# usb-dongle.net
KiCad netlist of a schematic drawn in EAGLE
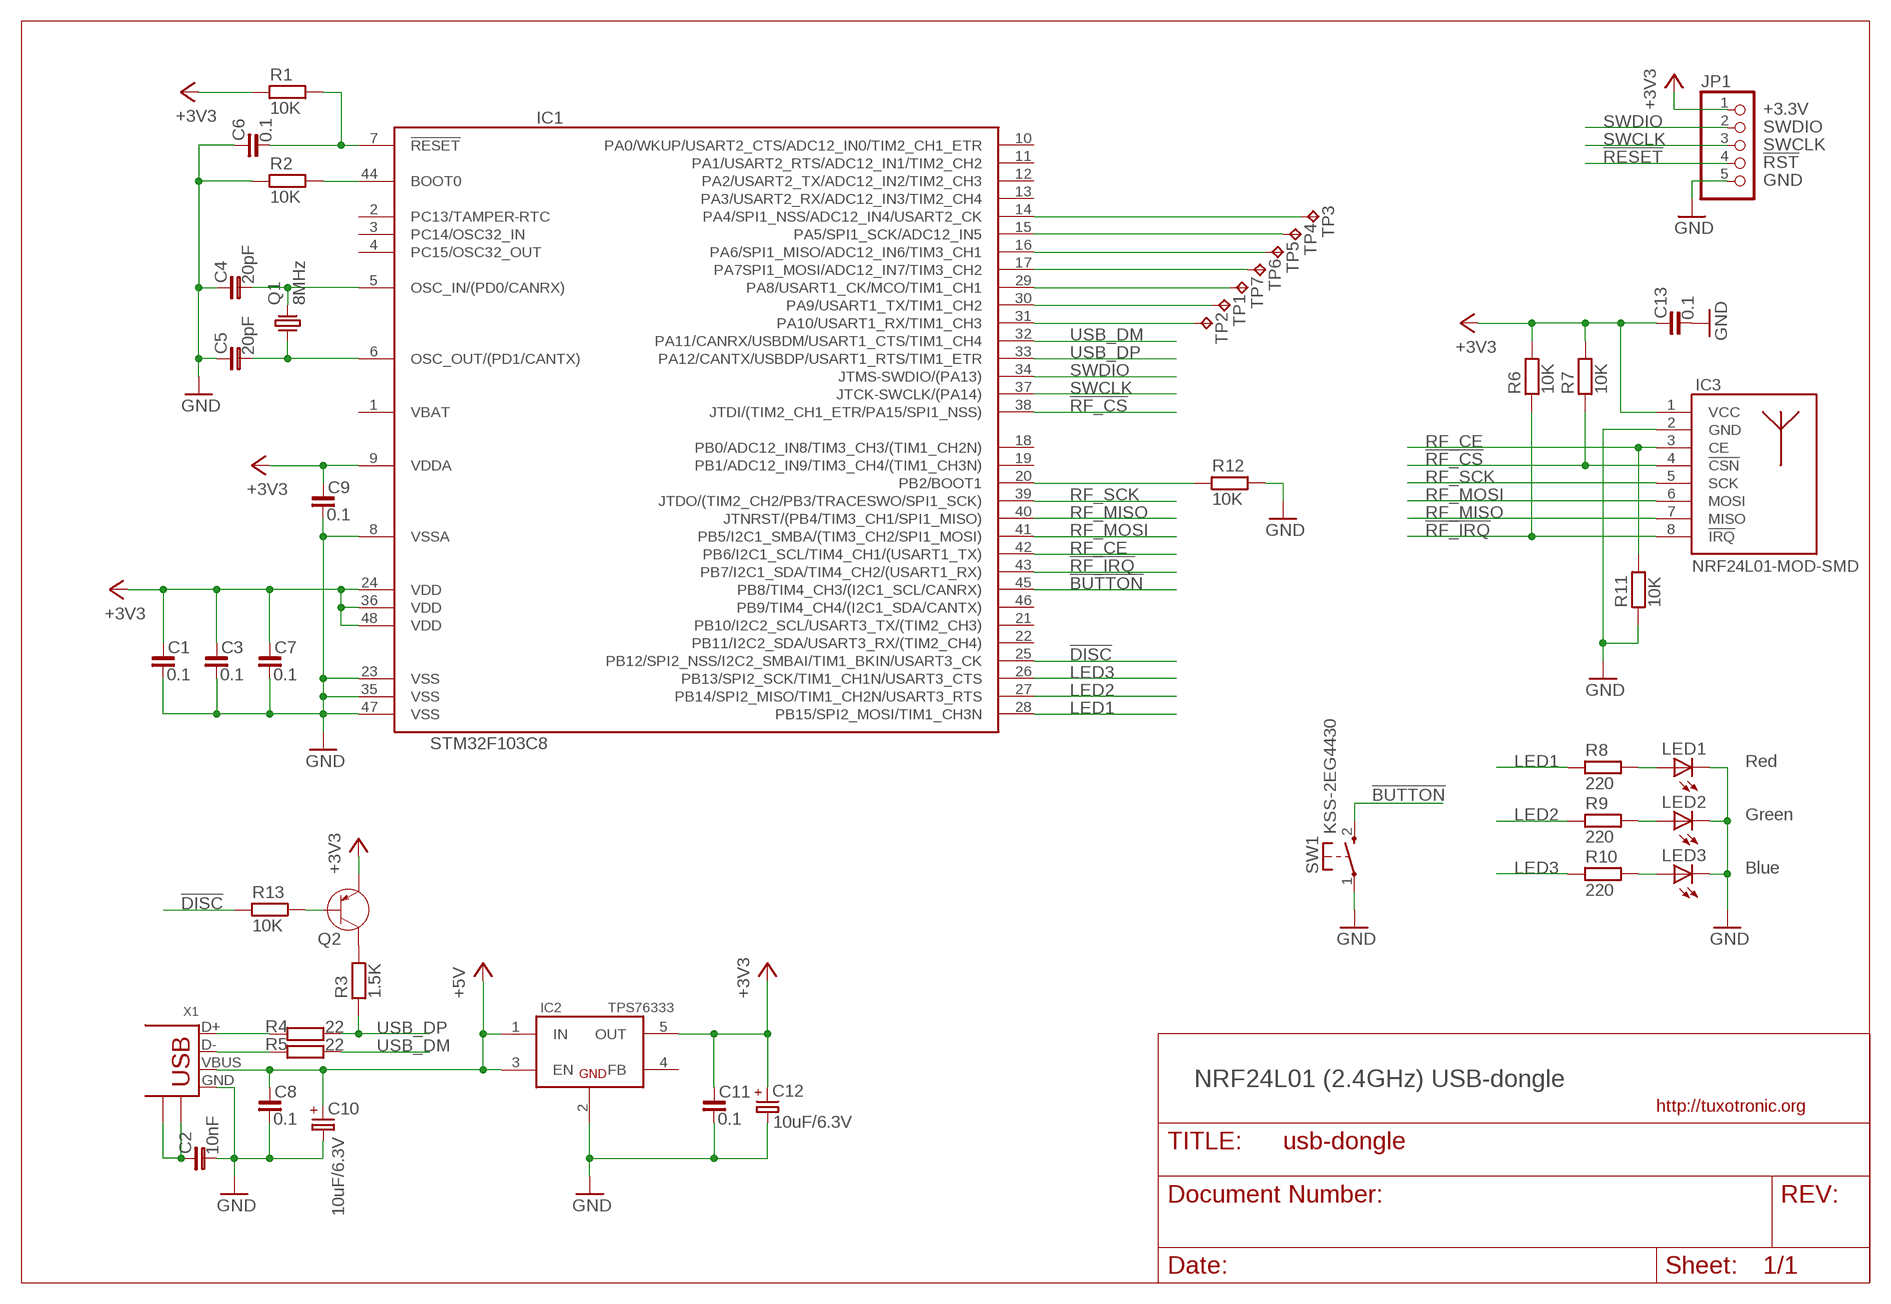
[diagram p0: schematic, sheet 1]

(export (version "E")
  (design (tool "Eeschema 10.0.6"))
  (components
    (comp (ref "C1")
      (value "0.1")
      (footprint "eagle-import:C0603")
      (libsource (lib "eagle-import") (part "C_0603"))
    )
    (comp (ref "C2")
      (value "10nF")
      (footprint "eagle-import:C1206")
      (libsource (lib "eagle-import") (part "C_1206"))
    )
    (comp (ref "C3")
      (value "0.1")
      (footprint "eagle-import:C0603")
      (libsource (lib "eagle-import") (part "C_0603"))
    )
    (comp (ref "C4")
      (value "20pF")
      (footprint "eagle-import:C0603")
      (libsource (lib "eagle-import") (part "C_0603"))
    )
    (comp (ref "C5")
      (value "20pF")
      (footprint "eagle-import:C0603")
      (libsource (lib "eagle-import") (part "C_0603"))
    )
    (comp (ref "C6")
      (value "0.1")
      (footprint "eagle-import:C0603")
      (libsource (lib "eagle-import") (part "C_0603"))
    )
    (comp (ref "C7")
      (value "0.1")
      (footprint "eagle-import:C0603")
      (libsource (lib "eagle-import") (part "C_0603"))
    )
    (comp (ref "C8")
      (value "0.1")
      (footprint "eagle-import:C0603")
      (libsource (lib "eagle-import") (part "C_0603"))
    )
    (comp (ref "C9")
      (value "0.1")
      (footprint "eagle-import:C0603")
      (libsource (lib "eagle-import") (part "C_0603"))
    )
    (comp (ref "C10")
      (value "10uF/6.3V")
      (footprint "eagle-import:SMC_B")
      (libsource (lib "eagle-import") (part "CP_SMCB"))
    )
    (comp (ref "C11")
      (value "0.1")
      (footprint "eagle-import:C0603")
      (libsource (lib "eagle-import") (part "C_0603"))
    )
    (comp (ref "C12")
      (value "10uF/6.3V")
      (footprint "eagle-import:SMC_B")
      (libsource (lib "eagle-import") (part "CP_SMCB"))
    )
    (comp (ref "C13")
      (value "0.1")
      (footprint "eagle-import:C0603")
      (libsource (lib "eagle-import") (part "C_0603"))
    )
    (comp (ref "IC1")
      (value "STM32F103C8")
      (footprint "eagle-import:LQFP48")
      (libsource (lib "eagle-import") (part "STM32F103C8"))
    )
    (comp (ref "IC2")
      (value "TPS76333")
      (footprint "eagle-import:SOT23-5")
      (libsource (lib "eagle-import") (part "TPS76333"))
    )
    (comp (ref "IC3")
      (value "NRF24L01-MOD-SMD")
      (footprint "eagle-import:SMD8-MODULE")
      (libsource (lib "eagle-import") (part "NRF24L01-MOD-SMD"))
    )
    (comp (ref "JP1")
      (value "SWD-5_2.00")
      (footprint "eagle-import:1X05M")
      (libsource (lib "eagle-import") (part "SWD-5_2.00"))
    )
    (comp (ref "LED1")
      (value "LEDCHIPLED_0805")
      (footprint "eagle-import:CHIPLED_0805")
      (libsource (lib "eagle-import") (part "LEDCHIPLED_0805"))
    )
    (comp (ref "LED2")
      (value "LEDCHIPLED_0805")
      (footprint "eagle-import:CHIPLED_0805")
      (libsource (lib "eagle-import") (part "LEDCHIPLED_0805"))
    )
    (comp (ref "LED3")
      (value "LEDCHIPLED_0805")
      (footprint "eagle-import:CHIPLED_0805")
      (libsource (lib "eagle-import") (part "LEDCHIPLED_0805"))
    )
    (comp (ref "Q1")
      (value "8MHz")
      (footprint "eagle-import:HC49_S")
      (libsource (lib "eagle-import") (part "CRYSTAL-HC49S"))
    )
    (comp (ref "Q2")
      (value "PNP-SOT23")
      (footprint "eagle-import:SOT23")
      (libsource (lib "eagle-import") (part "PNP-SOT23"))
    )
    (comp (ref "R1")
      (value "10K")
      (footprint "eagle-import:R0603")
      (libsource (lib "eagle-import") (part "R_0603"))
    )
    (comp (ref "R2")
      (value "10K")
      (footprint "eagle-import:R0603")
      (libsource (lib "eagle-import") (part "R_0603"))
    )
    (comp (ref "R3")
      (value "1.5K")
      (footprint "eagle-import:R0603")
      (libsource (lib "eagle-import") (part "R_0603"))
    )
    (comp (ref "R4")
      (value "22")
      (footprint "eagle-import:R0603")
      (libsource (lib "eagle-import") (part "R_0603"))
    )
    (comp (ref "R5")
      (value "22")
      (footprint "eagle-import:R0603")
      (libsource (lib "eagle-import") (part "R_0603"))
    )
    (comp (ref "R6")
      (value "10K")
      (footprint "eagle-import:R0603")
      (libsource (lib "eagle-import") (part "R_0603"))
    )
    (comp (ref "R7")
      (value "10K")
      (footprint "eagle-import:R0603")
      (libsource (lib "eagle-import") (part "R_0603"))
    )
    (comp (ref "R8")
      (value "220")
      (footprint "eagle-import:R0603")
      (libsource (lib "eagle-import") (part "R_0603"))
    )
    (comp (ref "R9")
      (value "220")
      (footprint "eagle-import:R0603")
      (libsource (lib "eagle-import") (part "R_0603"))
    )
    (comp (ref "R10")
      (value "220")
      (footprint "eagle-import:R0603")
      (libsource (lib "eagle-import") (part "R_0603"))
    )
    (comp (ref "R11")
      (value "10K")
      (footprint "eagle-import:R0603")
      (libsource (lib "eagle-import") (part "R_0603"))
    )
    (comp (ref "R12")
      (value "10K")
      (footprint "eagle-import:R0603")
      (libsource (lib "eagle-import") (part "R_0603"))
    )
    (comp (ref "R13")
      (value "10K")
      (footprint "eagle-import:R0603")
      (libsource (lib "eagle-import") (part "R_0603"))
    )
    (comp (ref "SW1")
      (value "KSS-2EG4430")
      (footprint "eagle-import:KSS-2EG4430")
      (libsource (lib "eagle-import") (part "KSS-2EG4430"))
    )
    (comp (ref "TP1")
      (value "TPB1,27")
      (footprint "eagle-import:B1,27")
      (libsource (lib "eagle-import") (part "TPB1,27"))
    )
    (comp (ref "TP2")
      (value "TPB1,27")
      (footprint "eagle-import:B1,27")
      (libsource (lib "eagle-import") (part "TPB1,27"))
    )
    (comp (ref "TP3")
      (value "TPB1,27")
      (footprint "eagle-import:B1,27")
      (libsource (lib "eagle-import") (part "TPB1,27"))
    )
    (comp (ref "TP4")
      (value "TPB1,27")
      (footprint "eagle-import:B1,27")
      (libsource (lib "eagle-import") (part "TPB1,27"))
    )
    (comp (ref "TP5")
      (value "TPB1,27")
      (footprint "eagle-import:B1,27")
      (libsource (lib "eagle-import") (part "TPB1,27"))
    )
    (comp (ref "TP6")
      (value "TPB1,27")
      (footprint "eagle-import:B1,27")
      (libsource (lib "eagle-import") (part "TPB1,27"))
    )
    (comp (ref "TP7")
      (value "TPB1,27")
      (footprint "eagle-import:B1,27")
      (libsource (lib "eagle-import") (part "TPB1,27"))
    )
    (comp (ref "X1")
      (value "USB-MALE-A-H")
      (footprint "eagle-import:USB-A-MH")
      (libsource (lib "eagle-import") (part "USB-MALE-A-H"))
    )
  )
  (nets
    (net (code "1") (name "+3V3") (class "Default")
      (node (ref "C1") (pin "1") (pinfunction "1_1") (pintype "passive"))
      (node (ref "C11") (pin "1") (pinfunction "1_1") (pintype "passive"))
      (node (ref "C12") (pin "+") (pinfunction "+_+") (pintype "passive"))
      (node (ref "C13") (pin "1") (pinfunction "1_1") (pintype "passive"))
      (node (ref "C3") (pin "1") (pinfunction "1_1") (pintype "passive"))
      (node (ref "C7") (pin "1") (pinfunction "1_1") (pintype "passive"))
      (node (ref "C9") (pin "1") (pinfunction "1_1") (pintype "passive"))
      (node (ref "IC1") (pin "24") (pinfunction "VDD_24") (pintype "power_in"))
      (node (ref "IC1") (pin "36") (pinfunction "VDD_36") (pintype "power_in"))
      (node (ref "IC1") (pin "48") (pinfunction "VDD_48") (pintype "power_in"))
      (node (ref "IC1") (pin "9") (pinfunction "VDDA_9") (pintype "power_in"))
      (node (ref "IC2") (pin "5") (pinfunction "OUT_5") (pintype "power_in"))
      (node (ref "IC3") (pin "1") (pinfunction "VCC_1") (pintype "power_in"))
      (node (ref "JP1") (pin "1") (pinfunction "1_1") (pintype "passive"))
      (node (ref "Q2") (pin "2") (pinfunction "E_2") (pintype "passive"))
      (node (ref "R1") (pin "1") (pinfunction "1_1") (pintype "passive"))
      (node (ref "R6") (pin "2") (pinfunction "2_2") (pintype "passive"))
      (node (ref "R7") (pin "2") (pinfunction "2_2") (pintype "passive"))
    )
    (net (code "2") (name "+5V") (class "Default")
      (node (ref "C10") (pin "+") (pinfunction "+_+") (pintype "passive"))
      (node (ref "C8") (pin "1") (pinfunction "1_1") (pintype "passive"))
      (node (ref "IC2") (pin "1") (pinfunction "IN_1") (pintype "power_in"))
      (node (ref "IC2") (pin "3") (pinfunction "EN_3") (pintype "input"))
      (node (ref "X1") (pin "VBUS") (pinfunction "VBUS_VBUS") (pintype "passive"))
    )
    (net (code "3") (name "/LED1") (class "Default")
      (node (ref "IC1") (pin "28") (pinfunction "PB15/SPI2_MOSI/TIM1_CH3N_28") (pintype "bidirectional"))
      (node (ref "R8") (pin "1") (pinfunction "1_1") (pintype "passive"))
    )
    (net (code "4") (name "/LED2") (class "Default")
      (node (ref "IC1") (pin "27") (pinfunction "PB14/SPI2_MISO/TIM1_CH2N/USART3_RTS_27") (pintype "bidirectional"))
      (node (ref "R9") (pin "1") (pinfunction "1_1") (pintype "passive"))
    )
    (net (code "5") (name "/LED3") (class "Default")
      (node (ref "IC1") (pin "26") (pinfunction "PB13/SPI2_SCK/TIM1_CH1N/USART3_CTS_26") (pintype "bidirectional"))
      (node (ref "R10") (pin "1") (pinfunction "1_1") (pintype "passive"))
    )
    (net (code "6") (name "/RF_CE") (class "Default")
      (node (ref "IC1") (pin "42") (pinfunction "PB6/I2C1_SCL/TIM4_CH1/(USART1_TX)_42") (pintype "bidirectional"))
      (node (ref "IC3") (pin "3") (pinfunction "CE_3") (pintype "input"))
      (node (ref "R11") (pin "2") (pinfunction "2_2") (pintype "passive"))
    )
    (net (code "7") (name "/RF_MISO") (class "Default")
      (node (ref "IC1") (pin "40") (pinfunction "JTNRST/(PB4/TIM3_CH1/SPI1_MISO)_40") (pintype "bidirectional"))
      (node (ref "IC3") (pin "7") (pinfunction "MISO_7") (pintype "output"))
    )
    (net (code "8") (name "/RF_MOSI") (class "Default")
      (node (ref "IC1") (pin "41") (pinfunction "PB5/I2C1_SMBA/(TIM3_CH2/SPI1_MOSI)_41") (pintype "bidirectional"))
      (node (ref "IC3") (pin "6") (pinfunction "MOSI_6") (pintype "input"))
    )
    (net (code "9") (name "/RF_SCK") (class "Default")
      (node (ref "IC1") (pin "39") (pinfunction "JTDO/(TIM2_CH2/PB3/TRACESWO/SPI1_SCK)_39") (pintype "bidirectional"))
      (node (ref "IC3") (pin "5") (pinfunction "SCK_5") (pintype "input"))
    )
    (net (code "10") (name "/SWCLK") (class "Default")
      (node (ref "IC1") (pin "37") (pinfunction "JTCK-SWCLK/(PA14)_37") (pintype "bidirectional"))
      (node (ref "JP1") (pin "3") (pinfunction "3_3") (pintype "passive"))
    )
    (net (code "11") (name "/SWDIO") (class "Default")
      (node (ref "IC1") (pin "34") (pinfunction "JTMS-SWDIO/(PA13)_34") (pintype "bidirectional"))
      (node (ref "JP1") (pin "2") (pinfunction "2_2") (pintype "passive"))
    )
    (net (code "12") (name "/USB_DM") (class "Default")
      (node (ref "IC1") (pin "32") (pinfunction "PA11/CANRX/USBDM/USART1_CTS/TIM1_CH4_32") (pintype "bidirectional"))
      (node (ref "R5") (pin "2") (pinfunction "2_2") (pintype "passive"))
    )
    (net (code "13") (name "/USB_DP") (class "Default")
      (node (ref "IC1") (pin "33") (pinfunction "PA12/CANTX/USBDP/USART1_RTS/TIM1_ETR_33") (pintype "bidirectional"))
      (node (ref "R3") (pin "1") (pinfunction "1_1") (pintype "passive"))
      (node (ref "R4") (pin "2") (pinfunction "2_2") (pintype "passive"))
    )
    (net (code "14") (name "/VBAT") (class "Default")
      (node (ref "IC1") (pin "1") (pinfunction "VBAT_1") (pintype "power_in"))
    )
    (net (code "15") (name "/~{BUTTON}") (class "Default")
      (node (ref "IC1") (pin "45") (pinfunction "PB8/TIM4_CH3/(I2C1_SCL/CANRX)_45") (pintype "bidirectional"))
      (node (ref "SW1") (pin "2") (pinfunction "S_2") (pintype "passive"))
    )
    (net (code "16") (name "/~{DISC}") (class "Default")
      (node (ref "IC1") (pin "25") (pinfunction "PB12/SPI2_NSS/I2C2_SMBAI/TIM1_BKIN/USART3_CK_25") (pintype "bidirectional"))
      (node (ref "R13") (pin "1") (pinfunction "1_1") (pintype "passive"))
    )
    (net (code "17") (name "/~{RESET}") (class "Default")
      (node (ref "C6") (pin "2") (pinfunction "2_2") (pintype "passive"))
      (node (ref "IC1") (pin "7") (pinfunction "~{RESET}_7") (pintype "input"))
      (node (ref "JP1") (pin "4") (pinfunction "4_4") (pintype "passive"))
      (node (ref "R1") (pin "2") (pinfunction "2_2") (pintype "passive"))
    )
    (net (code "18") (name "/~{RF_CS}") (class "Default")
      (node (ref "IC1") (pin "38") (pinfunction "JTDI/(TIM2_CH1_ETR/PA15/SPI1_NSS)_38") (pintype "bidirectional"))
      (node (ref "IC3") (pin "4") (pinfunction "~{CSN}_4") (pintype "input"))
      (node (ref "R7") (pin "1") (pinfunction "1_1") (pintype "passive"))
    )
    (net (code "19") (name "/~{RF_IRQ}") (class "Default")
      (node (ref "IC1") (pin "43") (pinfunction "PB7/I2C1_SDA/TIM4_CH2/(USART1_RX)_43") (pintype "bidirectional"))
      (node (ref "IC3") (pin "8") (pinfunction "~{IRQ}_8") (pintype "open_collector"))
      (node (ref "R6") (pin "1") (pinfunction "1_1") (pintype "passive"))
    )
    (net (code "20") (name "GND") (class "Default")
      (node (ref "C1") (pin "2") (pinfunction "2_2") (pintype "passive"))
      (node (ref "C10") (pin "-") (pinfunction "-_-") (pintype "passive"))
      (node (ref "C11") (pin "2") (pinfunction "2_2") (pintype "passive"))
      (node (ref "C12") (pin "-") (pinfunction "-_-") (pintype "passive"))
      (node (ref "C13") (pin "2") (pinfunction "2_2") (pintype "passive"))
      (node (ref "C2") (pin "2") (pinfunction "2_2") (pintype "passive"))
      (node (ref "C3") (pin "2") (pinfunction "2_2") (pintype "passive"))
      (node (ref "C4") (pin "1") (pinfunction "1_1") (pintype "passive"))
      (node (ref "C5") (pin "1") (pinfunction "1_1") (pintype "passive"))
      (node (ref "C6") (pin "1") (pinfunction "1_1") (pintype "passive"))
      (node (ref "C7") (pin "2") (pinfunction "2_2") (pintype "passive"))
      (node (ref "C8") (pin "2") (pinfunction "2_2") (pintype "passive"))
      (node (ref "C9") (pin "2") (pinfunction "2_2") (pintype "passive"))
      (node (ref "IC1") (pin "23") (pinfunction "VSS_23") (pintype "power_in"))
      (node (ref "IC1") (pin "35") (pinfunction "VSS_35") (pintype "power_in"))
      (node (ref "IC1") (pin "47") (pinfunction "VSS_47") (pintype "power_in"))
      (node (ref "IC1") (pin "8") (pinfunction "VSSA_8") (pintype "power_in"))
      (node (ref "IC2") (pin "2") (pinfunction "GND_2") (pintype "power_in"))
      (node (ref "IC3") (pin "2") (pinfunction "GND_2") (pintype "power_in"))
      (node (ref "JP1") (pin "5") (pinfunction "5_5") (pintype "passive"))
      (node (ref "LED1") (pin "C") (pinfunction "C_C") (pintype "passive"))
      (node (ref "LED2") (pin "C") (pinfunction "C_C") (pintype "passive"))
      (node (ref "LED3") (pin "C") (pinfunction "C_C") (pintype "passive"))
      (node (ref "R11") (pin "1") (pinfunction "1_1") (pintype "passive"))
      (node (ref "R12") (pin "2") (pinfunction "2_2") (pintype "passive"))
      (node (ref "R2") (pin "1") (pinfunction "1_1") (pintype "passive"))
      (node (ref "SW1") (pin "1") (pinfunction "P_1") (pintype "passive"))
      (node (ref "X1") (pin "GND") (pinfunction "GND_GND") (pintype "passive"))
    )
    (net (code "21") (name "Net-(IC1-BOOT0)") (class "Default")
      (node (ref "IC1") (pin "44") (pinfunction "BOOT0_44") (pintype "input"))
      (node (ref "R2") (pin "2") (pinfunction "2_2") (pintype "passive"))
    )
    (net (code "22") (name "Net-(IC1-OSC_IN{slash}(PD0{slash}CANRX))") (class "Default")
      (node (ref "C4") (pin "2") (pinfunction "2_2") (pintype "passive"))
      (node (ref "IC1") (pin "5") (pinfunction "OSC_IN/(PD0/CANRX)_5") (pintype "input"))
      (node (ref "Q1") (pin "2") (pinfunction "2_2") (pintype "passive"))
    )
    (net (code "23") (name "Net-(IC1-OSC_OUT{slash}(PD1{slash}CANTX))") (class "Default")
      (node (ref "C5") (pin "2") (pinfunction "2_2") (pintype "passive"))
      (node (ref "IC1") (pin "6") (pinfunction "OSC_OUT/(PD1/CANTX)_6") (pintype "output"))
      (node (ref "Q1") (pin "1") (pinfunction "1_1") (pintype "passive"))
    )
    (net (code "24") (name "Net-(IC1-PA4{slash}SPI1_NSS{slash}ADC12_IN4{slash}USART2_CK)") (class "Default")
      (node (ref "IC1") (pin "14") (pinfunction "PA4/SPI1_NSS/ADC12_IN4/USART2_CK_14") (pintype "bidirectional"))
      (node (ref "TP3") (pin "PP") (pinfunction "TP_PP") (pintype "input"))
    )
    (net (code "25") (name "Net-(IC1-PA5{slash}SPI1_SCK{slash}ADC12_IN5)") (class "Default")
      (node (ref "IC1") (pin "15") (pinfunction "PA5/SPI1_SCK/ADC12_IN5_15") (pintype "bidirectional"))
      (node (ref "TP4") (pin "PP") (pinfunction "TP_PP") (pintype "input"))
    )
    (net (code "26") (name "Net-(IC1-PA6{slash}SPI1_MISO{slash}ADC12_IN6{slash}TIM3_CH1)") (class "Default")
      (node (ref "IC1") (pin "16") (pinfunction "PA6/SPI1_MISO/ADC12_IN6/TIM3_CH1_16") (pintype "bidirectional"))
      (node (ref "TP5") (pin "PP") (pinfunction "TP_PP") (pintype "input"))
    )
    (net (code "27") (name "Net-(IC1-PA7SPI1_MOSI{slash}ADC12_IN7{slash}TIM3_CH2)") (class "Default")
      (node (ref "IC1") (pin "17") (pinfunction "PA7SPI1_MOSI/ADC12_IN7/TIM3_CH2_17") (pintype "bidirectional"))
      (node (ref "TP6") (pin "PP") (pinfunction "TP_PP") (pintype "input"))
    )
    (net (code "28") (name "Net-(IC1-PA8{slash}USART1_CK{slash}MCO{slash}TIM1_CH1)") (class "Default")
      (node (ref "IC1") (pin "29") (pinfunction "PA8/USART1_CK/MCO/TIM1_CH1_29") (pintype "bidirectional"))
      (node (ref "TP7") (pin "PP") (pinfunction "TP_PP") (pintype "input"))
    )
    (net (code "29") (name "Net-(IC1-PA9{slash}USART1_TX{slash}TIM1_CH2)") (class "Default")
      (node (ref "IC1") (pin "30") (pinfunction "PA9/USART1_TX/TIM1_CH2_30") (pintype "bidirectional"))
      (node (ref "TP1") (pin "PP") (pinfunction "TP_PP") (pintype "input"))
    )
    (net (code "30") (name "Net-(IC1-PA10{slash}USART1_RX{slash}TIM1_CH3)") (class "Default")
      (node (ref "IC1") (pin "31") (pinfunction "PA10/USART1_RX/TIM1_CH3_31") (pintype "bidirectional"))
      (node (ref "TP2") (pin "PP") (pinfunction "TP_PP") (pintype "input"))
    )
    (net (code "31") (name "Net-(IC1-PB2{slash}BOOT1)") (class "Default")
      (node (ref "IC1") (pin "20") (pinfunction "PB2/BOOT1_20") (pintype "bidirectional"))
      (node (ref "R12") (pin "1") (pinfunction "1_1") (pintype "passive"))
    )
    (net (code "32") (name "Net-(LED1-PadA)") (class "Default")
      (node (ref "LED1") (pin "A") (pinfunction "A_A") (pintype "passive"))
      (node (ref "R8") (pin "2") (pinfunction "2_2") (pintype "passive"))
    )
    (net (code "33") (name "Net-(LED2-PadA)") (class "Default")
      (node (ref "LED2") (pin "A") (pinfunction "A_A") (pintype "passive"))
      (node (ref "R9") (pin "2") (pinfunction "2_2") (pintype "passive"))
    )
    (net (code "34") (name "Net-(LED3-PadA)") (class "Default")
      (node (ref "LED3") (pin "A") (pinfunction "A_A") (pintype "passive"))
      (node (ref "R10") (pin "2") (pinfunction "2_2") (pintype "passive"))
    )
    (net (code "35") (name "Net-(Q2-B)") (class "Default")
      (node (ref "Q2") (pin "1") (pinfunction "B_1") (pintype "passive"))
      (node (ref "R13") (pin "2") (pinfunction "2_2") (pintype "passive"))
    )
    (net (code "36") (name "Net-(Q2-C)") (class "Default")
      (node (ref "Q2") (pin "3") (pinfunction "C_3") (pintype "passive"))
      (node (ref "R3") (pin "2") (pinfunction "2_2") (pintype "passive"))
    )
    (net (code "37") (name "Net-(R4-Pad1)") (class "Default")
      (node (ref "R4") (pin "1") (pinfunction "1_1") (pintype "passive"))
      (node (ref "X1") (pin "D+") (pinfunction "D+_D+") (pintype "passive"))
    )
    (net (code "38") (name "Net-(R5-Pad1)") (class "Default")
      (node (ref "R5") (pin "1") (pinfunction "1_1") (pintype "passive"))
      (node (ref "X1") (pin "D-") (pinfunction "D-_D-") (pintype "passive"))
    )
    (net (code "39") (name "Net-(X1-P$1)") (class "Default")
      (node (ref "C2") (pin "1") (pinfunction "1_1") (pintype "passive"))
      (node (ref "X1") (pin "P$5") (pinfunction "P$1_P$5") (pintype "passive"))
      (node (ref "X1") (pin "P$6") (pinfunction "P$2_P$6") (pintype "passive"))
    )
    (net (code "40") (name "unconnected-(IC1-PA0{slash}WKUP{slash}USART2_CTS{slash}ADC12_IN0{slash}TIM2_CH1_ETR-Pad10)") (class "Default")
      (node (ref "IC1") (pin "10") (pinfunction "PA0/WKUP/USART2_CTS/ADC12_IN0/TIM2_CH1_ETR_10") (pintype "bidirectional"))
    )
    (net (code "41") (name "unconnected-(IC1-PA1{slash}USART2_RTS{slash}ADC12_IN1{slash}TIM2_CH2-Pad11)") (class "Default")
      (node (ref "IC1") (pin "11") (pinfunction "PA1/USART2_RTS/ADC12_IN1/TIM2_CH2_11") (pintype "bidirectional"))
    )
    (net (code "42") (name "unconnected-(IC1-PA2{slash}USART2_TX{slash}ADC12_IN2{slash}TIM2_CH3-Pad12)") (class "Default")
      (node (ref "IC1") (pin "12") (pinfunction "PA2/USART2_TX/ADC12_IN2/TIM2_CH3_12") (pintype "bidirectional"))
    )
    (net (code "43") (name "unconnected-(IC1-PA3{slash}USART2_RX{slash}ADC12_IN3{slash}TIM2_CH4-Pad13)") (class "Default")
      (node (ref "IC1") (pin "13") (pinfunction "PA3/USART2_RX/ADC12_IN3/TIM2_CH4_13") (pintype "bidirectional"))
    )
    (net (code "44") (name "unconnected-(IC1-PB0{slash}ADC12_IN8{slash}TIM3_CH3{slash}(TIM1_CH2N)-Pad18)") (class "Default")
      (node (ref "IC1") (pin "18") (pinfunction "PB0/ADC12_IN8/TIM3_CH3/(TIM1_CH2N)_18") (pintype "bidirectional"))
    )
    (net (code "45") (name "unconnected-(IC1-PB1{slash}ADC12_IN9{slash}TIM3_CH4{slash}(TIM1_CH3N)-Pad19)") (class "Default")
      (node (ref "IC1") (pin "19") (pinfunction "PB1/ADC12_IN9/TIM3_CH4/(TIM1_CH3N)_19") (pintype "bidirectional"))
    )
    (net (code "46") (name "unconnected-(IC1-PB9{slash}TIM4_CH4{slash}(I2C1_SDA{slash}CANTX)-Pad46)") (class "Default")
      (node (ref "IC1") (pin "46") (pinfunction "PB9/TIM4_CH4/(I2C1_SDA/CANTX)_46") (pintype "bidirectional"))
    )
    (net (code "47") (name "unconnected-(IC1-PB10{slash}I2C2_SCL{slash}USART3_TX{slash}(TIM2_CH3)-Pad21)") (class "Default")
      (node (ref "IC1") (pin "21") (pinfunction "PB10/I2C2_SCL/USART3_TX/(TIM2_CH3)_21") (pintype "bidirectional"))
    )
    (net (code "48") (name "unconnected-(IC1-PB11{slash}I2C2_SDA{slash}USART3_RX{slash}(TIM2_CH4)-Pad22)") (class "Default")
      (node (ref "IC1") (pin "22") (pinfunction "PB11/I2C2_SDA/USART3_RX/(TIM2_CH4)_22") (pintype "bidirectional"))
    )
    (net (code "49") (name "unconnected-(IC1-PC13{slash}TAMPER-RTC-Pad2)") (class "Default")
      (node (ref "IC1") (pin "2") (pinfunction "PC13/TAMPER-RTC_2") (pintype "bidirectional"))
    )
    (net (code "50") (name "unconnected-(IC1-PC14{slash}OSC32_IN-Pad3)") (class "Default")
      (node (ref "IC1") (pin "3") (pinfunction "PC14/OSC32_IN_3") (pintype "bidirectional"))
    )
    (net (code "51") (name "unconnected-(IC1-PC15{slash}OSC32_OUT-Pad4)") (class "Default")
      (node (ref "IC1") (pin "4") (pinfunction "PC15/OSC32_OUT_4") (pintype "bidirectional"))
    )
    (net (code "52") (name "unconnected-(IC2-FB-Pad4)") (class "Default")
      (node (ref "IC2") (pin "4") (pinfunction "FB_4") (pintype "input"))
    )
  )
)
